# SpotLight.net
KiCad netlist of a schematic drawn in Altium Designer
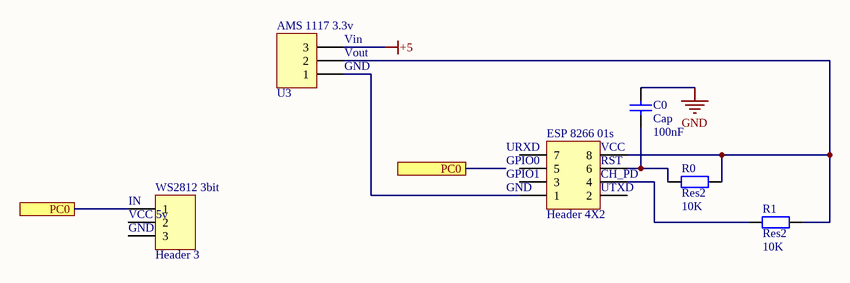
[diagram p0: SpotLight.SchDoc]

(export (version "E")
  (design (tool "Eeschema 10.0.6"))
  (components
    (comp (ref "AMS 1117 3.3v")
      (value "U3")
      (footprint "HDR1X3")
      (description "Header, 3-Pin")
      (fields (field (name "PUBLISHER") "Altium Limited"))
      (libsource (lib "Miscellaneous Connectors") (part "Header 3"))
    )
    (comp (ref "C0")
      (value "Cap")
      (footprint "RAD-0.3")
      (description "Capacitor")
      (fields (field (name "ALTIUM_VALUE") "100nF") (field (name "PUBLISHER") "Altium Limited"))
      (libsource (lib "Miscellaneous Devices") (part "Cap"))
    )
    (comp (ref "ESP 8266 01s")
      (value "Header 4X2")
      (footprint "HDR2X4")
      (description "Header, 4-Pin, Dual row")
      (fields (field (name "PUBLISHER") "Altium Limited"))
      (libsource (lib "Miscellaneous Connectors") (part "Header 4X2"))
    )
    (comp (ref "R0")
      (value "Res2")
      (footprint "AXIAL-0.4")
      (description "Resistor")
      (fields (field (name "ALTIUM_VALUE") "10K") (field (name "PUBLISHER") "Altium Limited"))
      (libsource (lib "Miscellaneous Devices") (part "Res2"))
    )
    (comp (ref "R1")
      (value "Res2")
      (footprint "AXIAL-0.4")
      (description "Resistor")
      (fields (field (name "ALTIUM_VALUE") "10K") (field (name "PUBLISHER") "Altium Limited"))
      (libsource (lib "Miscellaneous Devices") (part "Res2"))
    )
    (comp (ref "WS2812 3bit")
      (value "Header 3")
      (footprint "HDR1X3")
      (description "Header, 3-Pin")
      (fields (field (name "PUBLISHER") "Altium Limited"))
      (libsource (lib "") (part "Header 3_1"))
    )
  )
  (nets
    (net (code "1") (name "+5") (class "Default")
      (node (ref "AMS 1117 3.3v") (pin "3") (pinfunction "3_3") (pintype "passive"))
    )
    (net (code "2") (name "/PC0") (class "Default")
      (node (ref "WS2812 3bit") (pin "1") (pinfunction "1_1") (pintype "passive"))
    )
    (net (code "3") (name "GND") (class "Default")
      (node (ref "C0") (pin "2") (pinfunction "2_2") (pintype "passive"))
    )
    (net (code "4") (name "Net-(AMS 1117 3.3v-Pad1)") (class "Default")
      (node (ref "AMS 1117 3.3v") (pin "1") (pinfunction "1_1") (pintype "passive"))
      (node (ref "ESP 8266 01s") (pin "1") (pinfunction "1_1") (pintype "passive"))
    )
    (net (code "5") (name "Net-(AMS 1117 3.3v-Pad2)") (class "Default")
      (node (ref "AMS 1117 3.3v") (pin "2") (pinfunction "2_2") (pintype "passive"))
      (node (ref "ESP 8266 01s") (pin "8") (pinfunction "8_8") (pintype "passive"))
      (node (ref "R0") (pin "1") (pinfunction "1_1") (pintype "passive"))
      (node (ref "R1") (pin "1") (pinfunction "1_1") (pintype "passive"))
    )
    (net (code "6") (name "Net-(C0-Pad1)") (class "Default")
      (node (ref "C0") (pin "1") (pinfunction "1_1") (pintype "passive"))
      (node (ref "ESP 8266 01s") (pin "6") (pinfunction "6_6") (pintype "passive"))
      (node (ref "R0") (pin "2") (pinfunction "2_2") (pintype "passive"))
    )
    (net (code "7") (name "Net-(ESP 8266 01s-Pad4)") (class "Default")
      (node (ref "ESP 8266 01s") (pin "4") (pinfunction "4_4") (pintype "passive"))
      (node (ref "R1") (pin "2") (pinfunction "2_2") (pintype "passive"))
    )
    (net (code "8") (name "unconnected-(ESP 8266 01s-Pad2)") (class "Default")
      (node (ref "ESP 8266 01s") (pin "2") (pinfunction "2_2") (pintype "passive"))
    )
    (net (code "9") (name "unconnected-(ESP 8266 01s-Pad3)") (class "Default")
      (node (ref "ESP 8266 01s") (pin "3") (pinfunction "3_3") (pintype "passive"))
    )
    (net (code "10") (name "unconnected-(ESP 8266 01s-Pad5)") (class "Default")
      (node (ref "ESP 8266 01s") (pin "5") (pinfunction "5_5") (pintype "passive"))
    )
    (net (code "11") (name "unconnected-(ESP 8266 01s-Pad7)") (class "Default")
      (node (ref "ESP 8266 01s") (pin "7") (pinfunction "7_7") (pintype "passive"))
    )
    (net (code "12") (name "unconnected-(WS2812 3bit-Pad2)") (class "Default")
      (node (ref "WS2812 3bit") (pin "2") (pinfunction "2_2") (pintype "passive"))
    )
    (net (code "13") (name "unconnected-(WS2812 3bit-Pad3)") (class "Default")
      (node (ref "WS2812 3bit") (pin "3") (pinfunction "3_3") (pintype "passive"))
    )
  )
)
